# 3rd_SCHEMATIC_EP.net
KiCad netlist of a schematic drawn in EAGLE
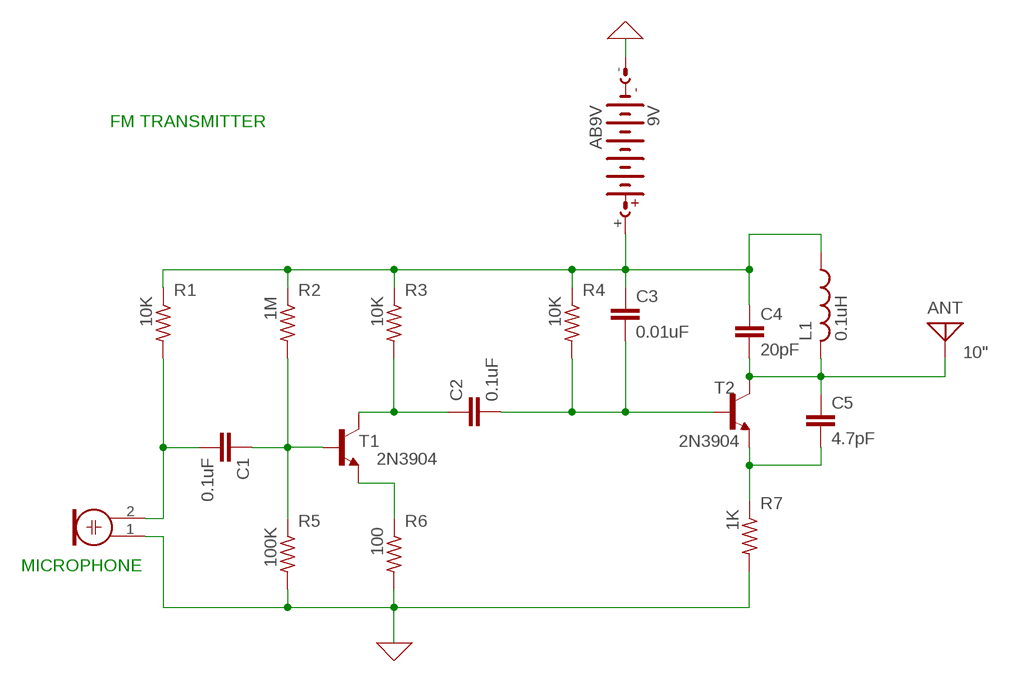
[diagram p0: schematic, sheet 1]

(export (version "E")
  (design (tool "Eeschema 10.0.6"))
  (components
    (comp (ref "9V")
      (value "AB9V")
      (footprint "eagle-import:AB9V")
      (libsource (lib "eagle-import") (part "AB9V"))
    )
    (comp (ref "ANT")
      (value "10\"")
      (footprint "eagle-import:PAD-01")
      (libsource (lib "eagle-import") (part "ANTENNA"))
    )
    (comp (ref "C1")
      (value "0.1uF")
      (footprint "eagle-import:C2.5-2")
      (libsource (lib "eagle-import") (part "C2.5/2"))
    )
    (comp (ref "C2")
      (value "0.1uF")
      (footprint "eagle-import:C2.5-2")
      (libsource (lib "eagle-import") (part "C2.5/2"))
    )
    (comp (ref "C3")
      (value "0.01uF")
      (footprint "eagle-import:C2.5-2")
      (libsource (lib "eagle-import") (part "C2.5/2"))
    )
    (comp (ref "C4")
      (value "20pF")
      (footprint "eagle-import:C2.5-2")
      (libsource (lib "eagle-import") (part "C2.5/2"))
    )
    (comp (ref "C5")
      (value "4.7pF")
      (footprint "eagle-import:C2.5-2")
      (libsource (lib "eagle-import") (part "C2.5/2"))
    )
    (comp (ref "L1")
      (value "0.1uH")
      (footprint "eagle-import:0207_7")
      (libsource (lib "eagle-import") (part "L-US0207/7"))
    )
    (comp (ref "MICROPHONE")
      (value "ELECTRET_MICROPHON-F6050AP")
      (footprint "eagle-import:F6050AP")
      (libsource (lib "eagle-import") (part "ELECTRET_MICROPHON-F6050AP"))
    )
    (comp (ref "R1")
      (value "10K")
      (footprint "eagle-import:R0603")
      (libsource (lib "eagle-import") (part "R-US_R0603"))
    )
    (comp (ref "R2")
      (value "1M")
      (footprint "eagle-import:R0603")
      (libsource (lib "eagle-import") (part "R-US_R0603"))
    )
    (comp (ref "R3")
      (value "10K")
      (footprint "eagle-import:R0603")
      (libsource (lib "eagle-import") (part "R-US_R0603"))
    )
    (comp (ref "R4")
      (value "10K")
      (footprint "eagle-import:R0603")
      (libsource (lib "eagle-import") (part "R-US_R0603"))
    )
    (comp (ref "R5")
      (value "100K")
      (footprint "eagle-import:R0603")
      (libsource (lib "eagle-import") (part "R-US_R0603"))
    )
    (comp (ref "R6")
      (value "100")
      (footprint "eagle-import:R0603")
      (libsource (lib "eagle-import") (part "R-US_R0603"))
    )
    (comp (ref "R7")
      (value "1K")
      (footprint "eagle-import:R0603")
      (libsource (lib "eagle-import") (part "R-US_R0603"))
    )
    (comp (ref "T1")
      (value "2N3904")
      (footprint "eagle-import:TO92")
      (libsource (lib "eagle-import") (part "2N3904"))
    )
    (comp (ref "T2")
      (value "2N3904")
      (footprint "eagle-import:TO92")
      (libsource (lib "eagle-import") (part "2N3904"))
    )
  )
  (nets
    (net (code "1") (name "GND") (class "Default")
      (node (ref "9V") (pin "-") (pinfunction "-_-") (pintype "passive"))
      (node (ref "MICROPHONE") (pin "1") (pinfunction "1_1") (pintype "passive"))
      (node (ref "R5") (pin "2") (pinfunction "2_2") (pintype "passive"))
      (node (ref "R6") (pin "2") (pinfunction "2_2") (pintype "passive"))
      (node (ref "R7") (pin "2") (pinfunction "2_2") (pintype "passive"))
    )
    (net (code "2") (name "Net-(9V-Pad+)") (class "Default")
      (node (ref "9V") (pin "+") (pinfunction "+_+") (pintype "passive"))
      (node (ref "C3") (pin "1") (pinfunction "1_1") (pintype "passive"))
      (node (ref "C4") (pin "1") (pinfunction "1_1") (pintype "passive"))
      (node (ref "L1") (pin "1") (pinfunction "1_1") (pintype "passive"))
      (node (ref "R1") (pin "1") (pinfunction "1_1") (pintype "passive"))
      (node (ref "R2") (pin "1") (pinfunction "1_1") (pintype "passive"))
      (node (ref "R3") (pin "1") (pinfunction "1_1") (pintype "passive"))
      (node (ref "R4") (pin "1") (pinfunction "1_1") (pintype "passive"))
    )
    (net (code "3") (name "Net-(C1-Pad2)") (class "Default")
      (node (ref "C1") (pin "2") (pinfunction "2_2") (pintype "passive"))
      (node (ref "MICROPHONE") (pin "2") (pinfunction "2_2") (pintype "passive"))
      (node (ref "R1") (pin "2") (pinfunction "2_2") (pintype "passive"))
    )
    (net (code "4") (name "Net-(T1-B)") (class "Default")
      (node (ref "C1") (pin "1") (pinfunction "1_1") (pintype "passive"))
      (node (ref "R2") (pin "2") (pinfunction "2_2") (pintype "passive"))
      (node (ref "R5") (pin "1") (pinfunction "1_1") (pintype "passive"))
      (node (ref "T1") (pin "2") (pinfunction "B_2") (pintype "passive"))
    )
    (net (code "5") (name "Net-(T1-C)") (class "Default")
      (node (ref "C2") (pin "1") (pinfunction "1_1") (pintype "passive"))
      (node (ref "R3") (pin "2") (pinfunction "2_2") (pintype "passive"))
      (node (ref "T1") (pin "1") (pinfunction "C_1") (pintype "passive"))
    )
    (net (code "6") (name "Net-(T1-E)") (class "Default")
      (node (ref "R6") (pin "1") (pinfunction "1_1") (pintype "passive"))
      (node (ref "T1") (pin "3") (pinfunction "E_3") (pintype "passive"))
    )
    (net (code "7") (name "Net-(T2-B)") (class "Default")
      (node (ref "C2") (pin "2") (pinfunction "2_2") (pintype "passive"))
      (node (ref "C3") (pin "2") (pinfunction "2_2") (pintype "passive"))
      (node (ref "R4") (pin "2") (pinfunction "2_2") (pintype "passive"))
      (node (ref "T2") (pin "2") (pinfunction "B_2") (pintype "passive"))
    )
    (net (code "8") (name "Net-(T2-C)") (class "Default")
      (node (ref "ANT") (pin "1") (pinfunction "1_1") (pintype "output"))
      (node (ref "C4") (pin "2") (pinfunction "2_2") (pintype "passive"))
      (node (ref "C5") (pin "1") (pinfunction "1_1") (pintype "passive"))
      (node (ref "L1") (pin "2") (pinfunction "2_2") (pintype "passive"))
      (node (ref "T2") (pin "1") (pinfunction "C_1") (pintype "passive"))
    )
    (net (code "9") (name "Net-(T2-E)") (class "Default")
      (node (ref "C5") (pin "2") (pinfunction "2_2") (pintype "passive"))
      (node (ref "R7") (pin "1") (pinfunction "1_1") (pintype "passive"))
      (node (ref "T2") (pin "3") (pinfunction "E_3") (pintype "passive"))
    )
  )
)
